# h_bridge.net
KiCad netlist of a schematic drawn in EAGLE
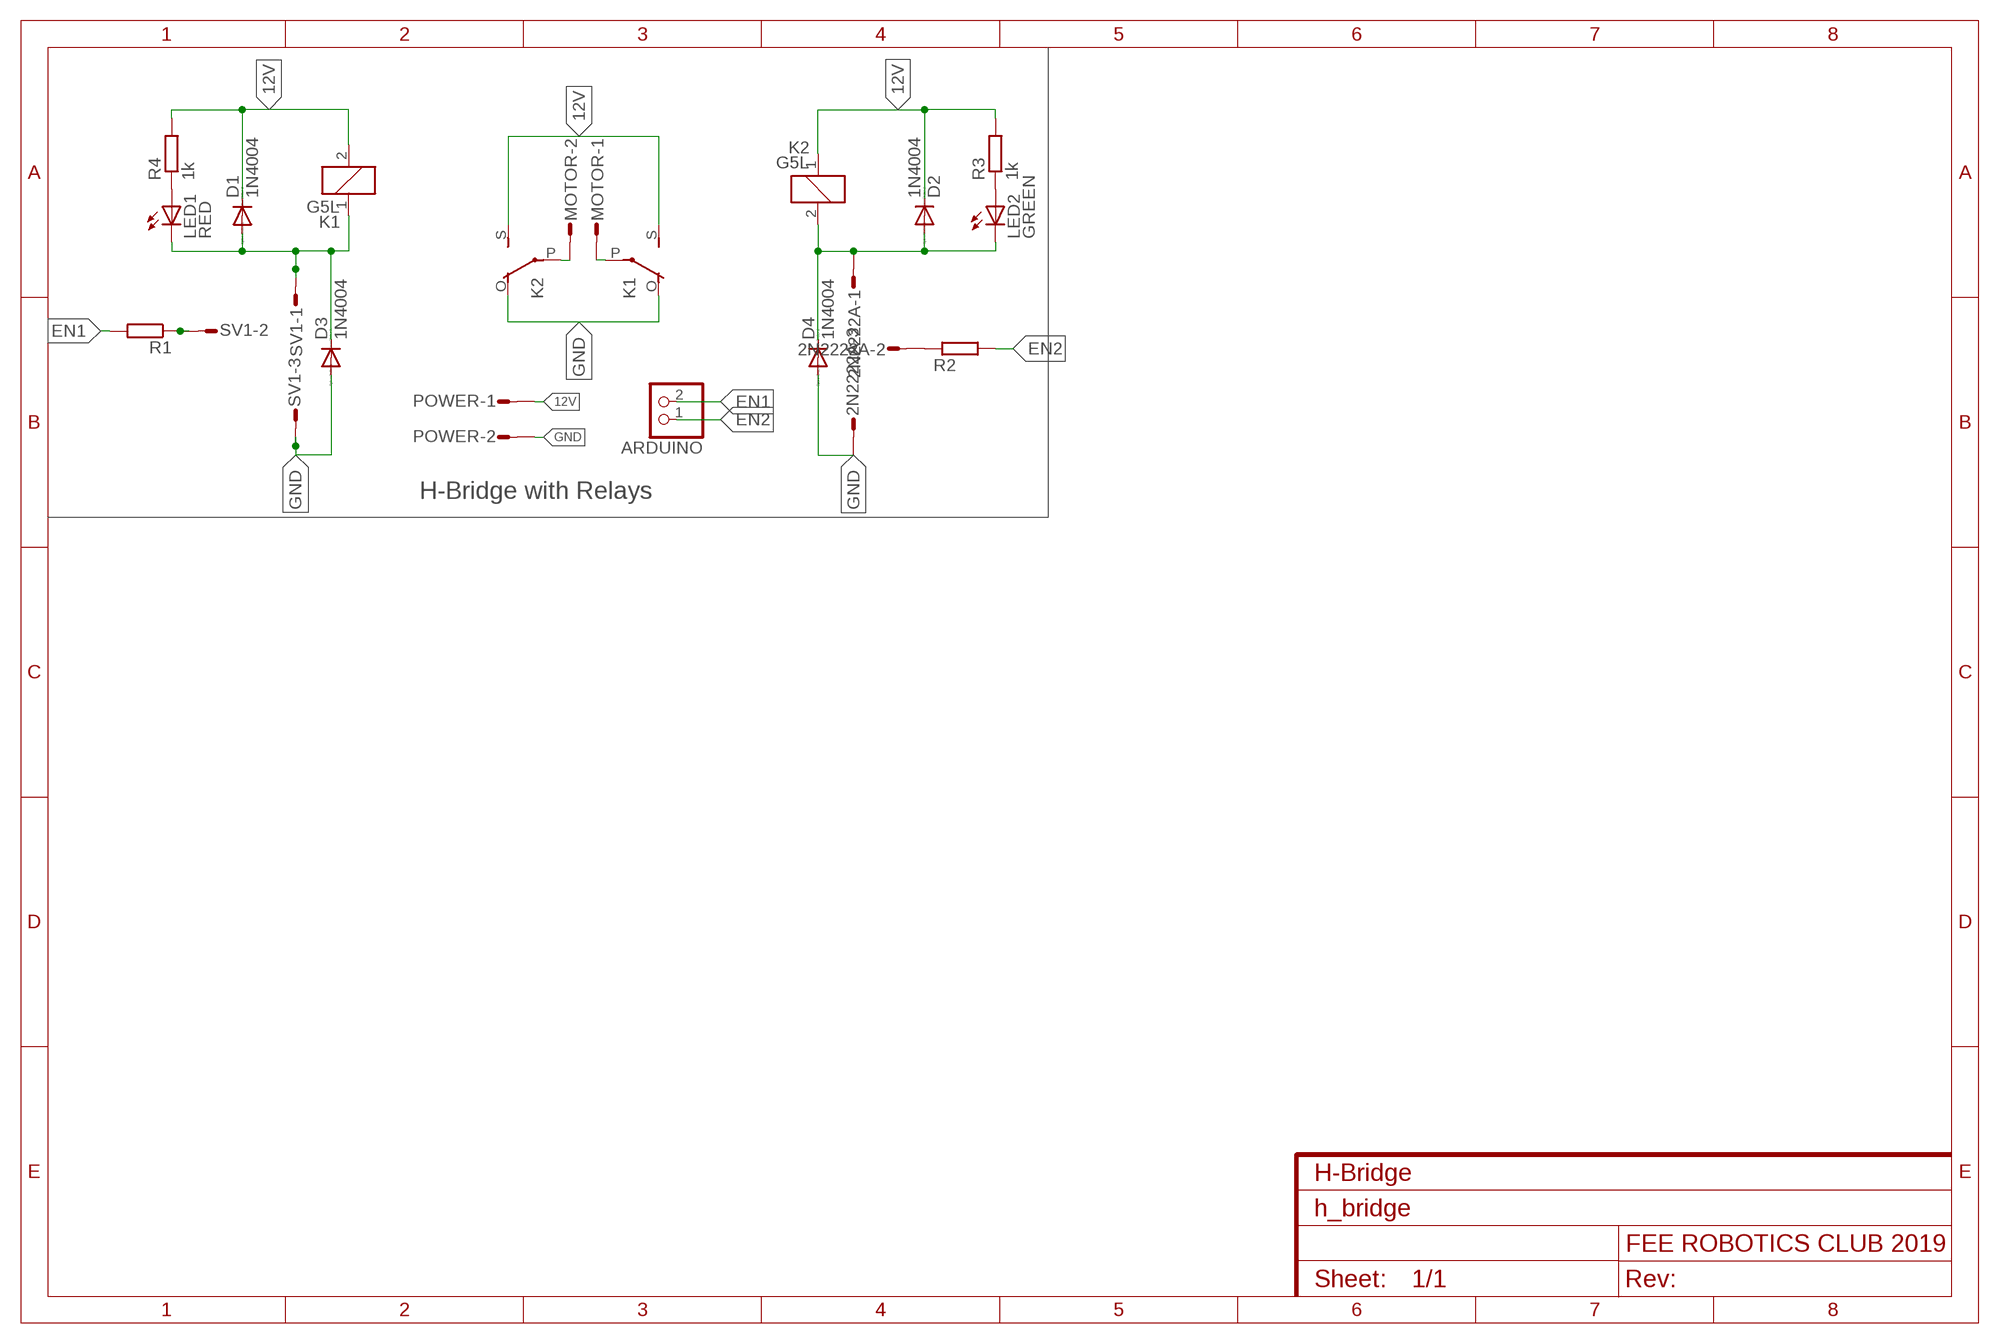
[diagram p0: schematic, sheet 1]

(export (version "E")
  (design (tool "Eeschema 10.0.6"))
  (components
    (comp (ref "2N2222A")
      (value "MT6-3")
      (footprint "eagle-import:MT6-3")
      (libsource (lib "eagle-import") (part "MT6-3"))
    )
    (comp (ref "ARDUINO")
      (value "PINHD-1X2")
      (footprint "eagle-import:1X02")
      (libsource (lib "eagle-import") (part "PINHD-1X2"))
    )
    (comp (ref "D1")
      (value "1N4004")
      (footprint "eagle-import:DO41-10")
      (libsource (lib "eagle-import") (part "1N4004"))
    )
    (comp (ref "D2")
      (value "1N4004")
      (footprint "eagle-import:DO41-10")
      (libsource (lib "eagle-import") (part "1N4004"))
    )
    (comp (ref "D3")
      (value "1N4004")
      (footprint "eagle-import:DO41-10")
      (libsource (lib "eagle-import") (part "1N4004"))
    )
    (comp (ref "D4")
      (value "1N4004")
      (footprint "eagle-import:DO41-10")
      (libsource (lib "eagle-import") (part "1N4004"))
    )
    (comp (ref "K1")
      (value "G5L")
      (footprint "eagle-import:G5LE")
      (libsource (lib "eagle-import") (part "G5L"))
    )
    (comp (ref "K2")
      (value "G5L")
      (footprint "eagle-import:G5LE")
      (libsource (lib "eagle-import") (part "G5L"))
    )
    (comp (ref "LED1")
      (value "RED")
      (footprint "eagle-import:LED3MM")
      (libsource (lib "eagle-import") (part "LED3MM"))
    )
    (comp (ref "LED2")
      (value "GREEN")
      (footprint "eagle-import:LED3MM")
      (libsource (lib "eagle-import") (part "LED3MM"))
    )
    (comp (ref "MOTOR")
      (value "L02P")
      (footprint "eagle-import:L02P")
      (libsource (lib "eagle-import") (part "L02P"))
    )
    (comp (ref "POWER")
      (value "L02P")
      (footprint "eagle-import:L02P")
      (libsource (lib "eagle-import") (part "L02P"))
    )
    (comp (ref "R1")
      (value "R-EU_0207/7")
      (footprint "eagle-import:0207_7")
      (libsource (lib "eagle-import") (part "R-EU_0207/7"))
    )
    (comp (ref "R2")
      (value "R-EU_0207/7")
      (footprint "eagle-import:0207_7")
      (libsource (lib "eagle-import") (part "R-EU_0207/7"))
    )
    (comp (ref "R3")
      (value "1k")
      (footprint "eagle-import:0207_7")
      (libsource (lib "eagle-import") (part "R-EU_0207/7"))
    )
    (comp (ref "R4")
      (value "1k")
      (footprint "eagle-import:0207_7")
      (libsource (lib "eagle-import") (part "R-EU_0207/7"))
    )
    (comp (ref "SV1")
      (value "MT6-3")
      (footprint "eagle-import:MT6-3")
      (libsource (lib "eagle-import") (part "MT6-3"))
    )
  )
  (nets
    (net (code "1") (name "12V") (class "Default")
      (node (ref "D1") (pin "C") (pinfunction "C_C") (pintype "passive"))
      (node (ref "D2") (pin "C") (pinfunction "C_C") (pintype "passive"))
      (node (ref "K1") (pin "2") (pinfunction "2_2") (pintype "passive"))
      (node (ref "K1") (pin "S") (pinfunction "S_S") (pintype "passive"))
      (node (ref "K2") (pin "1") (pinfunction "1_1") (pintype "passive"))
      (node (ref "K2") (pin "S") (pinfunction "S_S") (pintype "passive"))
      (node (ref "POWER") (pin "1") (pinfunction "S_1") (pintype "passive"))
      (node (ref "R3") (pin "2") (pinfunction "2_2") (pintype "passive"))
      (node (ref "R4") (pin "2") (pinfunction "2_2") (pintype "passive"))
    )
    (net (code "2") (name "EN1") (class "Default")
      (node (ref "ARDUINO") (pin "2") (pinfunction "2_2") (pintype "passive"))
      (node (ref "R1") (pin "2") (pinfunction "2_2") (pintype "passive"))
    )
    (net (code "3") (name "EN2") (class "Default")
      (node (ref "ARDUINO") (pin "1") (pinfunction "1_1") (pintype "passive"))
      (node (ref "R2") (pin "2") (pinfunction "2_2") (pintype "passive"))
    )
    (net (code "4") (name "GND") (class "Default")
      (node (ref "2N2222A") (pin "3") (pinfunction "S_3") (pintype "passive"))
      (node (ref "D3") (pin "A") (pinfunction "A_A") (pintype "passive"))
      (node (ref "D4") (pin "A") (pinfunction "A_A") (pintype "passive"))
      (node (ref "K1") (pin "O") (pinfunction "O_O") (pintype "passive"))
      (node (ref "K2") (pin "O") (pinfunction "O_O") (pintype "passive"))
      (node (ref "POWER") (pin "2") (pinfunction "S_2") (pintype "passive"))
      (node (ref "SV1") (pin "3") (pinfunction "S_3") (pintype "passive"))
    )
    (net (code "5") (name "Net-(2N2222AA-S)") (class "Default")
      (node (ref "2N2222A") (pin "1") (pinfunction "S_1") (pintype "passive"))
      (node (ref "D2") (pin "A") (pinfunction "A_A") (pintype "passive"))
      (node (ref "D4") (pin "C") (pinfunction "C_C") (pintype "passive"))
      (node (ref "K2") (pin "2") (pinfunction "2_2") (pintype "passive"))
      (node (ref "LED2") (pin "K") (pinfunction "C_K") (pintype "passive"))
    )
    (net (code "6") (name "Net-(2N2222AB-S)") (class "Default")
      (node (ref "2N2222A") (pin "2") (pinfunction "S_2") (pintype "passive"))
      (node (ref "R2") (pin "1") (pinfunction "1_1") (pintype "passive"))
    )
    (net (code "7") (name "Net-(LED1-C)") (class "Default")
      (node (ref "D1") (pin "A") (pinfunction "A_A") (pintype "passive"))
      (node (ref "D3") (pin "C") (pinfunction "C_C") (pintype "passive"))
      (node (ref "K1") (pin "1") (pinfunction "1_1") (pintype "passive"))
      (node (ref "LED1") (pin "K") (pinfunction "C_K") (pintype "passive"))
      (node (ref "SV1") (pin "1") (pinfunction "S_1") (pintype "passive"))
    )
    (net (code "8") (name "Net-(LED1-PadA)") (class "Default")
      (node (ref "LED1") (pin "A") (pinfunction "A_A") (pintype "passive"))
      (node (ref "R4") (pin "1") (pinfunction "1_1") (pintype "passive"))
    )
    (net (code "9") (name "Net-(LED2-PadA)") (class "Default")
      (node (ref "LED2") (pin "A") (pinfunction "A_A") (pintype "passive"))
      (node (ref "R3") (pin "1") (pinfunction "1_1") (pintype "passive"))
    )
    (net (code "10") (name "Net-(MOTORA-S)") (class "Default")
      (node (ref "K1") (pin "P") (pinfunction "P_P") (pintype "passive"))
      (node (ref "MOTOR") (pin "1") (pinfunction "S_1") (pintype "passive"))
    )
    (net (code "11") (name "Net-(MOTORB-S)") (class "Default")
      (node (ref "K2") (pin "P") (pinfunction "P_P") (pintype "passive"))
      (node (ref "MOTOR") (pin "2") (pinfunction "S_2") (pintype "passive"))
    )
    (net (code "12") (name "Net-(SV1B-S)") (class "Default")
      (node (ref "R1") (pin "1") (pinfunction "1_1") (pintype "passive"))
      (node (ref "SV1") (pin "2") (pinfunction "S_2") (pintype "passive"))
    )
  )
)
